# ISO_Power.net
KiCad netlist of a schematic drawn in Altium Designer
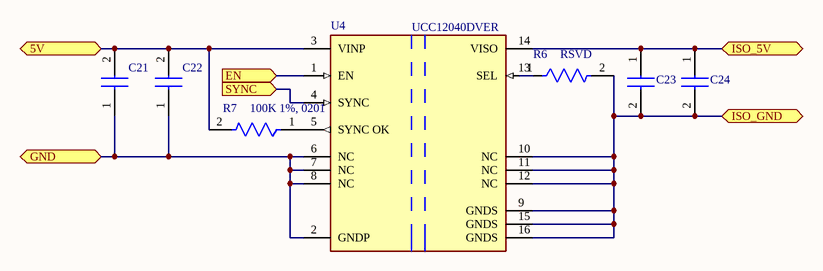
[diagram p0: ISO_Power.SchDoc]

(export (version "E")
  (design (tool "Eeschema 10.0.6"))
  (components
    (comp (ref "C21")
      (value "10 uF, 25V, X6S, 0402")
      (footprint "SamacSys:CAPC1005X70N")
      (description "Capacitor")
      (fields
        (field (name "MANUFACTURER_PART_NUMBER") "GRM155F51E104ZA01E")
        (field (name "MOUSER PART NUMBER") "81-GRM15F51E104ZA01E")
      )
      (libsource (lib "*") (part "GRM155F51E104ZA01E"))
    )
    (comp (ref "C22")
      (value "100 nF, 25V, X6S, 0201")
      (footprint "SamacSys:CAPC0603X33N")
      (description "Capacitor")
      (fields
        (field (name "MANUFACTURER_PART_NUMBER") "GRM033C81E104KE14D")
        (field (name "MOUSER PART NUMBER") "81-GRM33C81E104KE14D")
      )
      (libsource (lib "*") (part "GRM033C81E104KE14D"))
    )
    (comp (ref "C23")
      (value "100 nF, 25V, X6S, 0201")
      (footprint "SamacSys:CAPC0603X33N")
      (description "Capacitor")
      (fields
        (field (name "MANUFACTURER_PART_NUMBER") "GRM033C81E104KE14D")
        (field (name "MOUSER PART NUMBER") "81-GRM33C81E104KE14D")
      )
      (libsource (lib "*") (part "GRM033C81E104KE14D"))
    )
    (comp (ref "C24")
      (value "10 uF, 25V, X6S, 0402")
      (footprint "SamacSys:CAPC1005X70N")
      (description "Capacitor")
      (fields
        (field (name "MANUFACTURER_PART_NUMBER") "GRM155F51E104ZA01E")
        (field (name "MOUSER PART NUMBER") "81-GRM15F51E104ZA01E")
      )
      (libsource (lib "*") (part "GRM155F51E104ZA01E"))
    )
    (comp (ref "R6")
      (value "RSVD")
      (footprint "FP-ERJ1GN-IPC_A")
      (description "RES SMD 100K OHM 1% 1/20W 0201")
      (fields (field (name "TOLERANCE") "1%"))
      (libsource (lib "Altium Content Vault") (part "1029c3af85768c4190bb7ad29bc67b5"))
    )
    (comp (ref "R7")
      (value "100K 1%, 0201")
      (footprint "FP-ERJ1GN-IPC_A")
      (description "RES SMD 100K OHM 1% 1/20W 0201")
      (fields (field (name "TOLERANCE") "1%"))
      (libsource (lib "Altium Content Vault") (part "1029c3af85768c4190bb7ad29bc67b5"))
    )
    (comp (ref "U4")
      (value "UCC12040DVER")
      (footprint "FP-DVE0016A-MFG")
      (description "DC DC CONVERTER 3.3V 5V 500MW")
      (libsource (lib "Altium Content Vault") (part "cf9dcfd4a8b3775ff5e4cba6f3e7206"))
    )
  )
  (nets
    (net (code "1") (name "/5V") (class "Default")
      (node (ref "C21") (pin "2") (pinfunction "2_2") (pintype "passive"))
      (node (ref "C22") (pin "2") (pinfunction "2_2") (pintype "passive"))
      (node (ref "R7") (pin "2") (pinfunction "2_2") (pintype "passive"))
      (node (ref "U4") (pin "3") (pinfunction "VINP_3") (pintype "power_in"))
    )
    (net (code "2") (name "/EN") (class "Default")
      (node (ref "U4") (pin "1") (pinfunction "EN_1") (pintype "input"))
    )
    (net (code "3") (name "/GND") (class "Default")
      (node (ref "C21") (pin "1") (pinfunction "1_1") (pintype "passive"))
      (node (ref "C22") (pin "1") (pinfunction "1_1") (pintype "passive"))
      (node (ref "U4") (pin "2") (pinfunction "GNDP_2") (pintype "power_in"))
      (node (ref "U4") (pin "6") (pinfunction "NC_6") (pintype "passive"))
      (node (ref "U4") (pin "7") (pinfunction "NC_7") (pintype "passive"))
      (node (ref "U4") (pin "8") (pinfunction "NC_8") (pintype "passive"))
    )
    (net (code "4") (name "/ISO_5V") (class "Default")
      (node (ref "C23") (pin "1") (pinfunction "1_1") (pintype "passive"))
      (node (ref "C24") (pin "1") (pinfunction "1_1") (pintype "passive"))
      (node (ref "U4") (pin "14") (pinfunction "VISO_14") (pintype "power_in"))
    )
    (net (code "5") (name "/ISO_GND") (class "Default")
      (node (ref "C23") (pin "2") (pinfunction "2_2") (pintype "passive"))
      (node (ref "C24") (pin "2") (pinfunction "2_2") (pintype "passive"))
      (node (ref "R6") (pin "2") (pinfunction "2_2") (pintype "passive"))
      (node (ref "U4") (pin "10") (pinfunction "NC_10") (pintype "passive"))
      (node (ref "U4") (pin "11") (pinfunction "NC_11") (pintype "passive"))
      (node (ref "U4") (pin "12") (pinfunction "NC_12") (pintype "passive"))
      (node (ref "U4") (pin "15") (pinfunction "GNDS_15") (pintype "power_in"))
      (node (ref "U4") (pin "16") (pinfunction "GNDS_16") (pintype "power_in"))
      (node (ref "U4") (pin "9") (pinfunction "GNDS_9") (pintype "power_in"))
    )
    (net (code "6") (name "/SYNC") (class "Default")
      (node (ref "U4") (pin "4") (pinfunction "SYNC_4") (pintype "input"))
    )
    (net (code "7") (name "Net-(U4-SEL)") (class "Default")
      (node (ref "R6") (pin "1") (pinfunction "1_1") (pintype "passive"))
      (node (ref "U4") (pin "13") (pinfunction "SEL_13") (pintype "input"))
    )
    (net (code "8") (name "Net-(U4-SYNC_OK)") (class "Default")
      (node (ref "R7") (pin "1") (pinfunction "1_1") (pintype "passive"))
      (node (ref "U4") (pin "5") (pinfunction "SYNC_OK_5") (pintype "output"))
    )
  )
)
